# Magnetic_encoder.net
KiCad netlist of a schematic drawn in Altium Designer
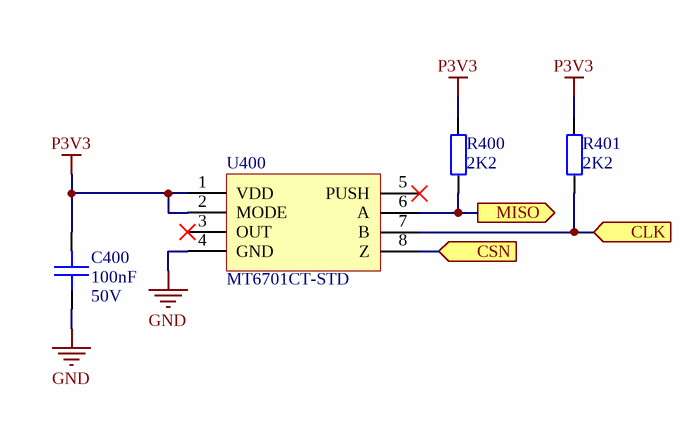
[diagram p0: Magnetic_encoder.SchDoc]

(export (version "E")
  (design (tool "Eeschema 10.0.6"))
  (components
    (comp (ref "C400")
      (value "100nF")
      (footprint "C0402")
      (description "General purpose ceramic capacitor")
      (fields
        (field (name "VOLTAGE") "50V")
        (field (name "MANUFACTURER") "Murata Electronics")
        (field (name "MANUFACTURER PART NO") "GRT155R71H104KE01D")
      )
      (libsource (lib "Moonlight_Library") (part "CAP"))
    )
    (comp (ref "R400")
      (value "2K2")
      (footprint "R0402")
      (description "General purpose resistor")
      (fields (field (name "MANUFACTURER PART NO") "Generic resistor") (field (name "Comment") "RES"))
      (libsource (lib "Moonlight_Library") (part "RES"))
    )
    (comp (ref "R401")
      (value "2K2")
      (footprint "R0402")
      (description "General purpose resistor")
      (fields (field (name "MANUFACTURER PART NO") "Generic resistor") (field (name "Comment") "RES"))
      (libsource (lib "Moonlight_Library") (part "RES"))
    )
    (comp (ref "U400")
      (value "MT6701")
      (footprint "SOP-8")
      (description "Hall effect absolute magnetic encoder")
      (fields (field (name "MANUFACTURER PART NO") "MT6701CT-STD") (field (name "MANUFACTURER") "MagnTek"))
      (libsource (lib "Moonlight_Library") (part "MT6701"))
    )
  )
  (nets
    (net (code "1") (name "/CLK") (class "Default")
      (node (ref "R401") (pin "1") (pintype "passive"))
      (node (ref "U400") (pin "7") (pinfunction "B_7") (pintype "passive"))
    )
    (net (code "2") (name "/CSN") (class "Default")
      (node (ref "U400") (pin "8") (pinfunction "Z_8") (pintype "passive"))
    )
    (net (code "3") (name "/MISO") (class "Default")
      (node (ref "R400") (pin "1") (pintype "passive"))
      (node (ref "U400") (pin "6") (pinfunction "A_6") (pintype "passive"))
    )
    (net (code "4") (name "GND") (class "Default")
      (node (ref "C400") (pin "2") (pinfunction "2_2") (pintype "passive"))
      (node (ref "U400") (pin "4") (pinfunction "GND_4") (pintype "passive"))
    )
    (net (code "5") (name "P3V3") (class "Default")
      (node (ref "C400") (pin "1") (pinfunction "1_1") (pintype "passive"))
      (node (ref "R400") (pin "2") (pintype "passive"))
      (node (ref "R401") (pin "2") (pintype "passive"))
      (node (ref "U400") (pin "1") (pinfunction "VDD_1") (pintype "passive"))
      (node (ref "U400") (pin "2") (pinfunction "MODE_2") (pintype "passive"))
    )
    (net (code "6") (name "unconnected-(U400-OUT-Pad3)") (class "Default")
      (node (ref "U400") (pin "3") (pinfunction "OUT_3") (pintype "passive+no_connect"))
    )
    (net (code "7") (name "unconnected-(U400-PUSH-Pad5)") (class "Default")
      (node (ref "U400") (pin "5") (pinfunction "PUSH_5") (pintype "passive+no_connect"))
    )
  )
)
